# MIDI.net
KiCad netlist of a schematic drawn in Altium Designer
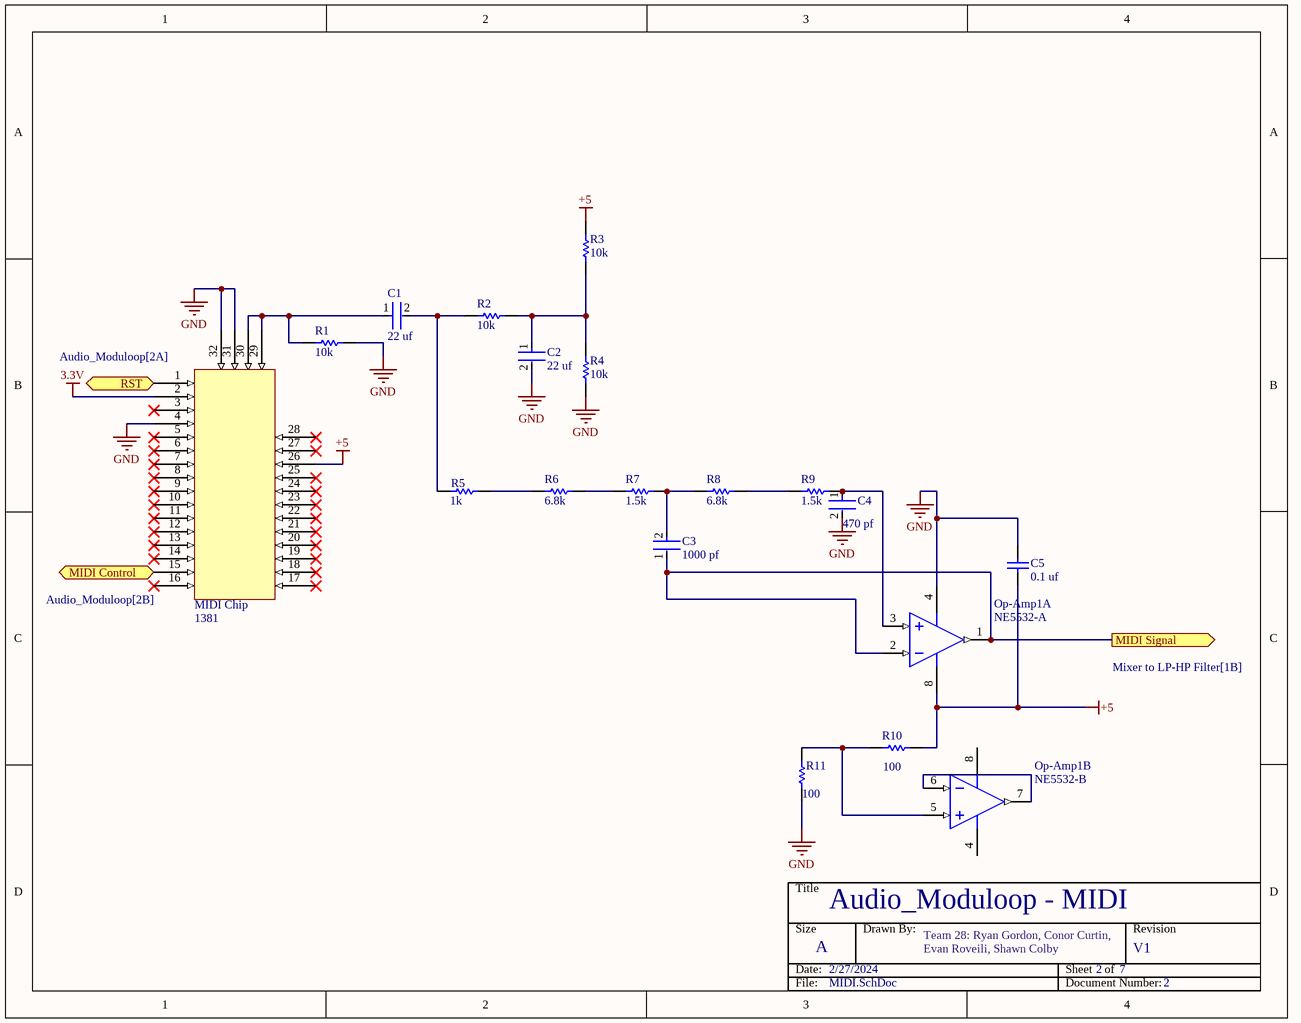
[diagram p0: MIDI.SchDoc]

(export (version "E")
  (design (tool "Eeschema 10.0.6"))
  (components
    (comp (ref "C1")
      (value "22 uf")
      (footprint "FP-RCEWM1-MFG")
      (description "CAP CER 22UF 25V X7R RADIAL")
      (fields (field (name "TOLERANCE") "20%"))
      (libsource (lib "Altium Content Vault") (part "02cd4be3c70576c341d710602a673aa"))
    )
    (comp (ref "C2")
      (value "22 uf")
      (footprint "FP-RCEWM1-MFG")
      (description "CAP CER 22UF 25V X7R RADIAL")
      (fields (field (name "TOLERANCE") "20%"))
      (libsource (lib "Altium Content Vault") (part "02cd4be3c70576c341d710602a673aa"))
    )
    (comp (ref "C3")
      (value "1000 pf")
      (footprint "FP-VY1102M35Y5UQ6TV0-MFG")
      (description "CAP CER 1000PF 760VAC Y5U RADIAL")
      (fields (field (name "VOLTAGE") "500V") (field (name "TOLERANCE") "20%"))
      (libsource (lib "Altium Content Vault") (part "6d4d395cd7362dd47ce0157d173177e"))
    )
    (comp (ref "C4")
      (value "470 pf")
      (footprint "FP-F471K33Y5RP6UK5R-MFG")
      (description "CAP CER 470PF 2KV Y5R RADIAL")
      (fields (field (name "TOLERANCE") "10%") (field (name "VOLTAGE") "2kV"))
      (libsource (lib "Altium Content Vault") (part "b4654b650e69147ec39a6b967a45e02"))
    )
    (comp (ref "C5")
      (value "0.1 uf")
      (footprint "AVX-SA115C104KAR")
      (fields (field (name "TOLERANCE") "±10%") (field (name "MANUFACTURER") "AVX"))
      (libsource (lib "Altium Content Vault") (part "CAP-NP-2"))
    )
    (comp (ref "MIDI Chip")
      (value "1381")
      (footprint "FEATHERWING")
      (description "Conn, Rect, PowerPoleHousing, PP180Series, Blue, 180A, 600V")
      (libsource (lib "Ryamgordon") (part "1381"))
    )
    (comp (ref "Op-Amp1")
      (value "NE5532-A")
      (footprint "ONSC-SOIC-8-751-07_V")
      (fields (field (name "MANUFACTURER") "On Semiconductor") (field (name "PARTNUMBER") "NE5532AD8R2G"))
      (libsource (lib "Altium Content Vault") (part "ONSC-NE5532-SOIC-8-751-07"))
    )
    (comp (ref "R1")
      (value "10k")
      (footprint "RESC2013X60X35NL10T20")
      (description "Chip Resistor, 10 KOhm, +/- 1%, 0.125 W, -55 to 155 degC, 0805 (2012 Metric), RoHS, Tape and Reel")
      (fields (field (name "MANUFACTURER") "Yageo"))
      (libsource (lib "Altium Content Vault") (part "RES-2"))
    )
    (comp (ref "R2")
      (value "10k")
      (footprint "RESC2013X60X35NL10T20")
      (description "Chip Resistor, 10 KOhm, +/- 1%, 0.125 W, -55 to 155 degC, 0805 (2012 Metric), RoHS, Tape and Reel")
      (fields (field (name "MANUFACTURER") "Yageo"))
      (libsource (lib "Altium Content Vault") (part "RES-2"))
    )
    (comp (ref "R3")
      (value "10k")
      (footprint "RESC2013X60X35NL10T20")
      (description "Chip Resistor, 10 KOhm, +/- 1%, 0.125 W, -55 to 155 degC, 0805 (2012 Metric), RoHS, Tape and Reel")
      (fields (field (name "MANUFACTURER") "Yageo"))
      (libsource (lib "Altium Content Vault") (part "RES-2"))
    )
    (comp (ref "R4")
      (value "10k")
      (footprint "RESC2013X60X35NL10T20")
      (description "Chip Resistor, 10 KOhm, +/- 1%, 0.125 W, -55 to 155 degC, 0805 (2012 Metric), RoHS, Tape and Reel")
      (fields (field (name "MANUFACTURER") "Yageo"))
      (libsource (lib "Altium Content Vault") (part "RES-2"))
    )
    (comp (ref "R5")
      (value "1k")
      (footprint "RESC2013X70X40ML20T20")
      (description "Chip Resistor, 1 KOhm, +/- 1%, 0.125 W, -55 to 155 degC, 0805 (2012 Metric), RoHS, Tape and Reel")
      (fields (field (name "MANUFACTURER") "Panasonic"))
      (libsource (lib "Altium Content Vault") (part "RES-2"))
    )
    (comp (ref "R6")
      (value "6.8k")
      (footprint "RESC2013X70X40LL20T20")
      (fields (field (name "MANUFACTURER") "Panasonic") (field (name "PART NUMBER") "ERJ6ENF6801V"))
      (libsource (lib "Altium Content Vault") (part "RES"))
    )
    (comp (ref "R7")
      (value "1.5k")
      (footprint "RESC2013X60X40LL20T25")
      (fields (field (name "MANUFACTURER") "Panasonic") (field (name "PART NUMBER") "ERA6AEB152V"))
      (libsource (lib "Altium Content Vault") (part "RES"))
    )
    (comp (ref "R8")
      (value "6.8k")
      (footprint "RESC2013X70X40LL20T20")
      (fields (field (name "MANUFACTURER") "Panasonic") (field (name "PART NUMBER") "ERJ6ENF6801V"))
      (libsource (lib "Altium Content Vault") (part "RES"))
    )
    (comp (ref "R9")
      (value "1.5k")
      (footprint "RESC2013X60X40LL20T25")
      (fields (field (name "MANUFACTURER") "Panasonic") (field (name "PART NUMBER") "ERA6AEB152V"))
      (libsource (lib "Altium Content Vault") (part "RES"))
    )
    (comp (ref "R10")
      (value "100")
      (footprint "RESC2013X60X40ML20T25")
      (fields (field (name "MANUFACTURER") "Panasonic") (field (name "PART NUMBER") "ERA6AEB101V"))
      (libsource (lib "Altium Content Vault") (part "RES"))
    )
    (comp (ref "R11")
      (value "100")
      (footprint "RESC2013X60X40ML20T25")
      (fields (field (name "MANUFACTURER") "Panasonic") (field (name "PART NUMBER") "ERA6AEB101V"))
      (libsource (lib "Altium Content Vault") (part "RES"))
    )
  )
  (nets
    (net (code "1") (name "+5") (class "Default")
      (node (ref "C5") (pin "1") (pinfunction "1_1") (pintype "passive"))
      (node (ref "MIDI Chip") (pin "26") (pintype "input"))
      (node (ref "Op-Amp1") (pin "8") (pinfunction "V+_8") (pintype "power_in"))
      (node (ref "R10") (pin "2") (pinfunction "2_2") (pintype "passive"))
      (node (ref "R3") (pin "1") (pinfunction "1_1") (pintype "passive"))
    )
    (net (code "2") (name "/MIDI Control") (class "Default")
      (node (ref "MIDI Chip") (pin "15") (pintype "input"))
    )
    (net (code "3") (name "/MIDI Signal") (class "Default")
      (node (ref "C3") (pin "1") (pinfunction "1_1") (pintype "passive"))
      (node (ref "Op-Amp1") (pin "1") (pinfunction "OUTA_1") (pintype "output"))
      (node (ref "Op-Amp1") (pin "2") (pinfunction "INA-_2") (pintype "input"))
    )
    (net (code "4") (name "/RST") (class "Default") (node (ref "MIDI Chip") (pin "1") (pintype "input")))
    (net (code "5") (name "3.3V") (class "Default") (node (ref "MIDI Chip") (pin "2") (pintype "input")))
    (net (code "6") (name "GND") (class "Default")
      (node (ref "C2") (pin "2") (pinfunction "2_2") (pintype "passive"))
      (node (ref "C4") (pin "2") (pinfunction "2_2") (pintype "passive"))
      (node (ref "C5") (pin "2") (pinfunction "2_2") (pintype "passive"))
      (node (ref "MIDI Chip") (pin "31") (pintype "input"))
      (node (ref "MIDI Chip") (pin "32") (pintype "input"))
      (node (ref "MIDI Chip") (pin "4") (pintype "input"))
      (node (ref "Op-Amp1") (pin "4") (pinfunction "V-_4") (pintype "power_in"))
      (node (ref "R1") (pin "2") (pinfunction "2_2") (pintype "passive"))
      (node (ref "R11") (pin "1") (pinfunction "1_1") (pintype "passive"))
      (node (ref "R4") (pin "2") (pinfunction "2_2") (pintype "passive"))
    )
    (net (code "7") (name "Net-(C1-Pad1)") (class "Default")
      (node (ref "C1") (pin "1") (pinfunction "1_1") (pintype "passive"))
      (node (ref "MIDI Chip") (pin "29") (pintype "input"))
      (node (ref "MIDI Chip") (pin "30") (pintype "input"))
      (node (ref "R1") (pin "1") (pinfunction "1_1") (pintype "passive"))
    )
    (net (code "8") (name "Net-(C1-Pad2)") (class "Default")
      (node (ref "C1") (pin "2") (pinfunction "2_2") (pintype "passive"))
      (node (ref "R2") (pin "1") (pinfunction "1_1") (pintype "passive"))
      (node (ref "R5") (pin "1") (pinfunction "1_1") (pintype "passive"))
    )
    (net (code "9") (name "Net-(C2-Pad1)") (class "Default")
      (node (ref "C2") (pin "1") (pinfunction "1_1") (pintype "passive"))
      (node (ref "R2") (pin "2") (pinfunction "2_2") (pintype "passive"))
      (node (ref "R3") (pin "2") (pinfunction "2_2") (pintype "passive"))
      (node (ref "R4") (pin "1") (pinfunction "1_1") (pintype "passive"))
    )
    (net (code "10") (name "Net-(C3-Pad2)") (class "Default")
      (node (ref "C3") (pin "2") (pinfunction "2_2") (pintype "passive"))
      (node (ref "R7") (pin "2") (pinfunction "2_2") (pintype "passive"))
      (node (ref "R8") (pin "1") (pinfunction "1_1") (pintype "passive"))
    )
    (net (code "11") (name "Net-(Op-Amp1A-INA+)") (class "Default")
      (node (ref "C4") (pin "1") (pinfunction "1_1") (pintype "passive"))
      (node (ref "Op-Amp1") (pin "3") (pinfunction "INA+_3") (pintype "input"))
      (node (ref "R9") (pin "2") (pinfunction "2_2") (pintype "passive"))
    )
    (net (code "12") (name "Net-(Op-Amp1B-INB+)") (class "Default")
      (node (ref "Op-Amp1") (pin "5") (pinfunction "INB+_5") (pintype "input"))
      (node (ref "R10") (pin "1") (pinfunction "1_1") (pintype "passive"))
      (node (ref "R11") (pin "2") (pinfunction "2_2") (pintype "passive"))
    )
    (net (code "13") (name "Net-(Op-Amp1B-INB-)") (class "Default")
      (node (ref "Op-Amp1") (pin "6") (pinfunction "INB-_6") (pintype "input"))
      (node (ref "Op-Amp1") (pin "7") (pinfunction "OUTB_7") (pintype "output"))
    )
    (net (code "14") (name "Net-(R5-Pad2)") (class "Default")
      (node (ref "R5") (pin "2") (pinfunction "2_2") (pintype "passive"))
      (node (ref "R6") (pin "1") (pinfunction "1_1") (pintype "passive"))
    )
    (net (code "15") (name "Net-(R6-Pad2)") (class "Default")
      (node (ref "R6") (pin "2") (pinfunction "2_2") (pintype "passive"))
      (node (ref "R7") (pin "1") (pinfunction "1_1") (pintype "passive"))
    )
    (net (code "16") (name "Net-(R8-Pad2)") (class "Default")
      (node (ref "R8") (pin "2") (pinfunction "2_2") (pintype "passive"))
      (node (ref "R9") (pin "1") (pinfunction "1_1") (pintype "passive"))
    )
    (net (code "17") (name "unconnected-(MIDI Chip-Pad3)") (class "Default")
      (node (ref "MIDI Chip") (pin "3") (pintype "input+no_connect"))
    )
    (net (code "18") (name "unconnected-(MIDI Chip-Pad5)") (class "Default")
      (node (ref "MIDI Chip") (pin "5") (pintype "input+no_connect"))
    )
    (net (code "19") (name "unconnected-(MIDI Chip-Pad6)") (class "Default")
      (node (ref "MIDI Chip") (pin "6") (pintype "input+no_connect"))
    )
    (net (code "20") (name "unconnected-(MIDI Chip-Pad7)") (class "Default")
      (node (ref "MIDI Chip") (pin "7") (pintype "input+no_connect"))
    )
    (net (code "21") (name "unconnected-(MIDI Chip-Pad8)") (class "Default")
      (node (ref "MIDI Chip") (pin "8") (pintype "input+no_connect"))
    )
    (net (code "22") (name "unconnected-(MIDI Chip-Pad9)") (class "Default")
      (node (ref "MIDI Chip") (pin "9") (pintype "input+no_connect"))
    )
    (net (code "23") (name "unconnected-(MIDI Chip-Pad10)") (class "Default")
      (node (ref "MIDI Chip") (pin "10") (pintype "input+no_connect"))
    )
    (net (code "24") (name "unconnected-(MIDI Chip-Pad11)") (class "Default")
      (node (ref "MIDI Chip") (pin "11") (pintype "input+no_connect"))
    )
    (net (code "25") (name "unconnected-(MIDI Chip-Pad12)") (class "Default")
      (node (ref "MIDI Chip") (pin "12") (pintype "input+no_connect"))
    )
    (net (code "26") (name "unconnected-(MIDI Chip-Pad13)") (class "Default")
      (node (ref "MIDI Chip") (pin "13") (pintype "input+no_connect"))
    )
    (net (code "27") (name "unconnected-(MIDI Chip-Pad14)") (class "Default")
      (node (ref "MIDI Chip") (pin "14") (pintype "input+no_connect"))
    )
    (net (code "28") (name "unconnected-(MIDI Chip-Pad16)") (class "Default")
      (node (ref "MIDI Chip") (pin "16") (pintype "input+no_connect"))
    )
    (net (code "29") (name "unconnected-(MIDI Chip-Pad17)") (class "Default")
      (node (ref "MIDI Chip") (pin "17") (pintype "input+no_connect"))
    )
    (net (code "30") (name "unconnected-(MIDI Chip-Pad18)") (class "Default")
      (node (ref "MIDI Chip") (pin "18") (pintype "input+no_connect"))
    )
    (net (code "31") (name "unconnected-(MIDI Chip-Pad19)") (class "Default")
      (node (ref "MIDI Chip") (pin "19") (pintype "input+no_connect"))
    )
    (net (code "32") (name "unconnected-(MIDI Chip-Pad20)") (class "Default")
      (node (ref "MIDI Chip") (pin "20") (pintype "input+no_connect"))
    )
    (net (code "33") (name "unconnected-(MIDI Chip-Pad21)") (class "Default")
      (node (ref "MIDI Chip") (pin "21") (pintype "input+no_connect"))
    )
    (net (code "34") (name "unconnected-(MIDI Chip-Pad22)") (class "Default")
      (node (ref "MIDI Chip") (pin "22") (pintype "input+no_connect"))
    )
    (net (code "35") (name "unconnected-(MIDI Chip-Pad23)") (class "Default")
      (node (ref "MIDI Chip") (pin "23") (pintype "input+no_connect"))
    )
    (net (code "36") (name "unconnected-(MIDI Chip-Pad24)") (class "Default")
      (node (ref "MIDI Chip") (pin "24") (pintype "input+no_connect"))
    )
    (net (code "37") (name "unconnected-(MIDI Chip-Pad25)") (class "Default")
      (node (ref "MIDI Chip") (pin "25") (pintype "input+no_connect"))
    )
    (net (code "38") (name "unconnected-(MIDI Chip-Pad27)") (class "Default")
      (node (ref "MIDI Chip") (pin "27") (pintype "input+no_connect"))
    )
    (net (code "39") (name "unconnected-(MIDI Chip-Pad28)") (class "Default")
      (node (ref "MIDI Chip") (pin "28") (pintype "input+no_connect"))
    )
    (net (code "40") (name "unconnected-(Op-Amp1B-V+-Pad8)") (class "Default")
      (node (ref "Op-Amp1") (pin "8") (pinfunction "V+_8") (pintype "power_in"))
    )
    (net (code "41") (name "unconnected-(Op-Amp1B-V--Pad4)") (class "Default")
      (node (ref "Op-Amp1") (pin "4") (pinfunction "V-_4") (pintype "power_in"))
    )
  )
)
